# APRSTracker_GPS.net
KiCad netlist of a schematic drawn in EAGLE
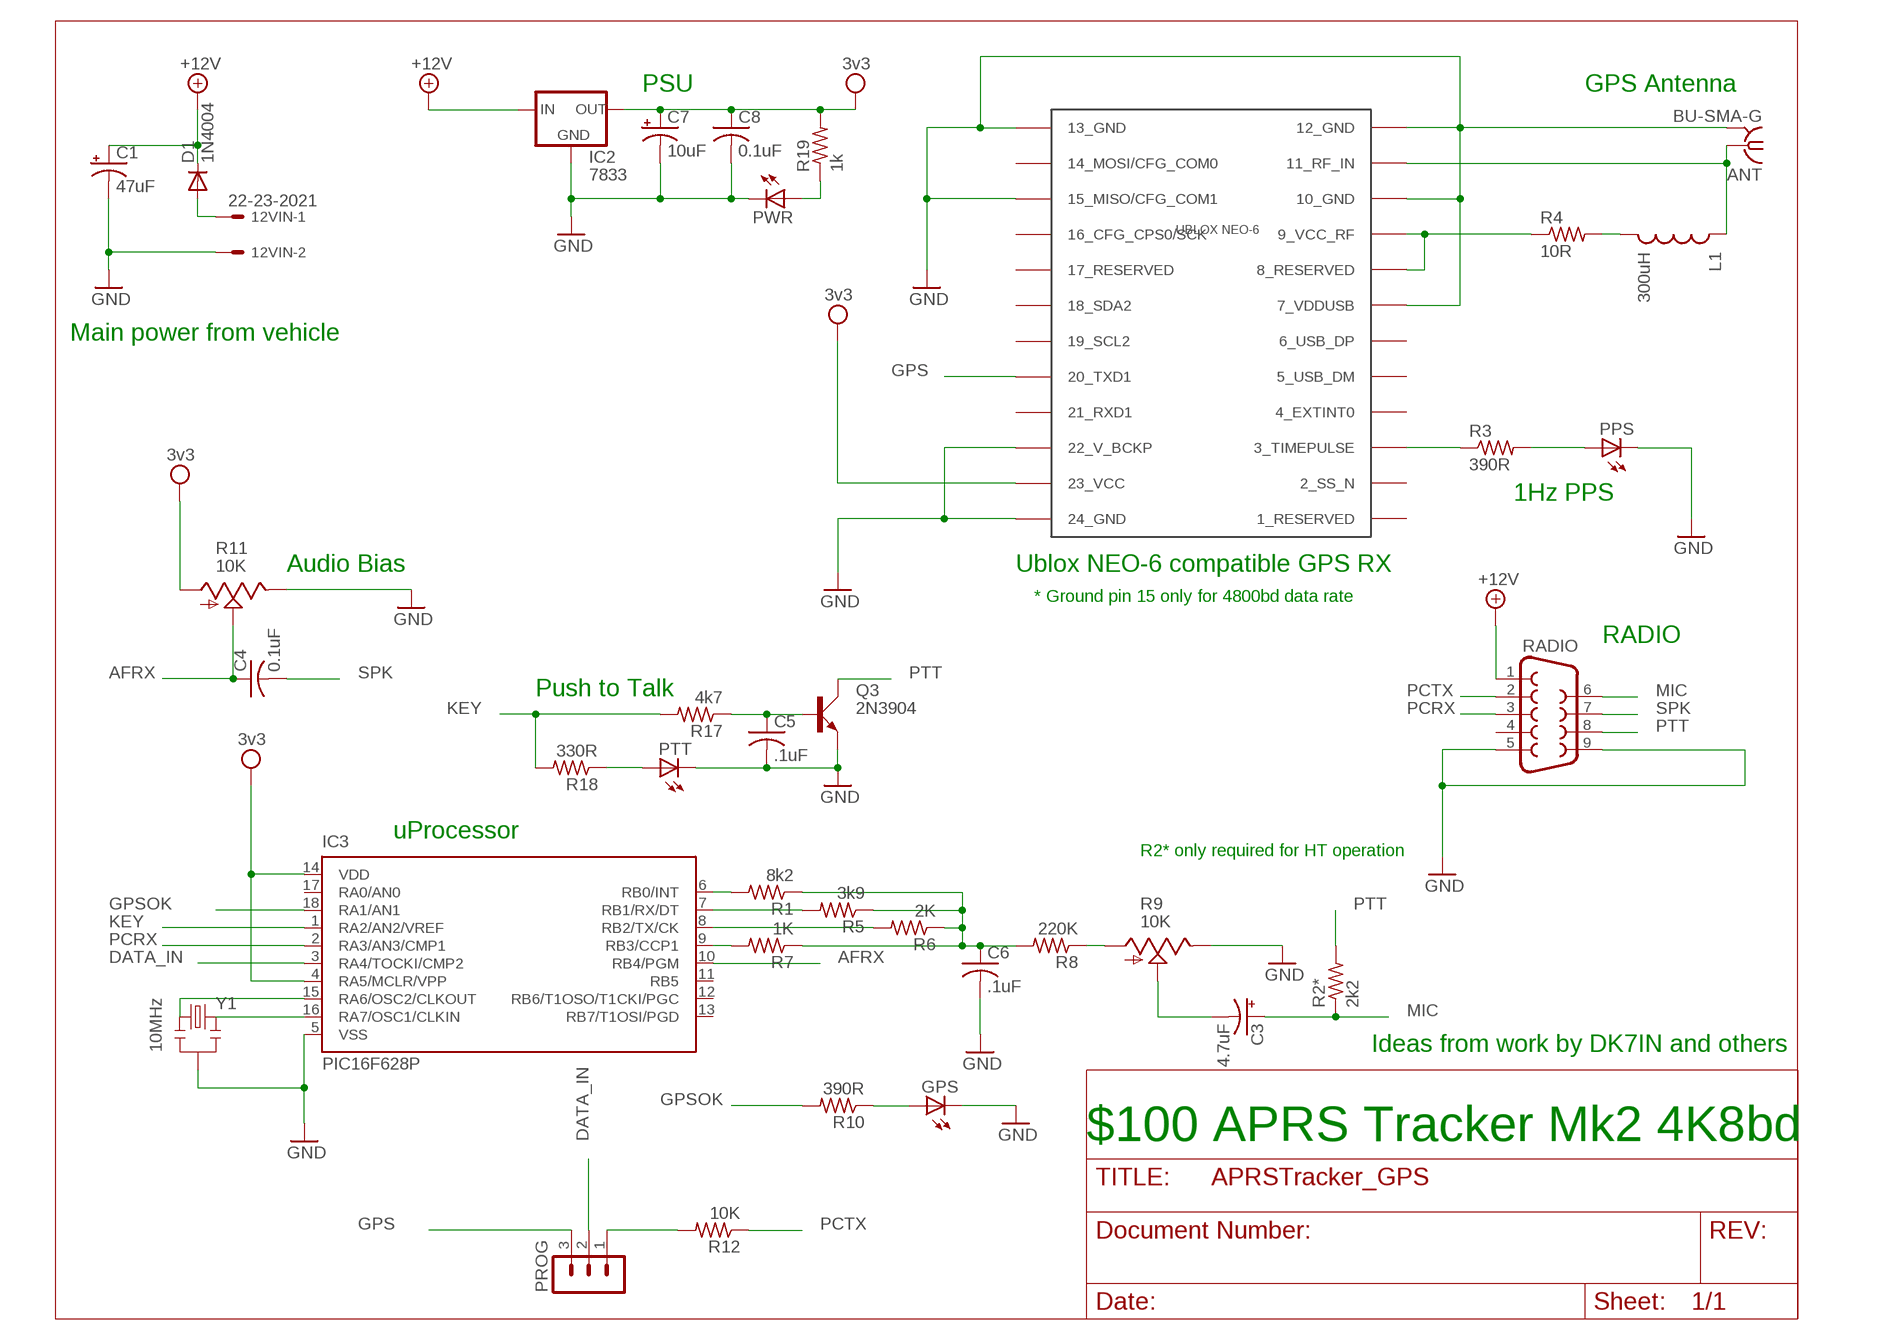
[diagram p0: schematic, sheet 1]

(export (version "E")
  (design (tool "Eeschema 10.0.6"))
  (components
    (comp (ref "12VIN")
      (value "22-23-2021")
      (footprint "eagle-import:22-23-2021")
      (fields (field (name "MF") "MOLEX"))
      (libsource (lib "eagle-import") (part "22-23-2021"))
    )
    (comp (ref "ANT")
      (value "BU-SMA-G")
      (footprint "eagle-import:BU-SMA-G")
      (libsource (lib "eagle-import") (part "BU-SMA-G"))
    )
    (comp (ref "C1")
      (value "47uF")
      (footprint "eagle-import:CPOL-RADIAL-10UF-25V")
      (libsource (lib "eagle-import") (part "CAP_POLPTH2"))
    )
    (comp (ref "C3")
      (value "4.7uF")
      (footprint "eagle-import:CPOL-RADIAL-10UF-25V")
      (libsource (lib "eagle-import") (part "CAP_POLPTH2"))
    )
    (comp (ref "C4")
      (value "0.1uF")
      (footprint "eagle-import:C025-025X050")
      (libsource (lib "eagle-import") (part "C-US025-025X050"))
    )
    (comp (ref "C5")
      (value ".1uF")
      (footprint "eagle-import:C025-025X050")
      (libsource (lib "eagle-import") (part "C-US025-025X050"))
    )
    (comp (ref "C6")
      (value ".1uF")
      (footprint "eagle-import:C025-025X050")
      (libsource (lib "eagle-import") (part "C-US025-025X050"))
    )
    (comp (ref "C7")
      (value "10uF")
      (footprint "eagle-import:CPOL-RADIAL-10UF-25V")
      (libsource (lib "eagle-import") (part "CAP_POLPTH2"))
    )
    (comp (ref "C8")
      (value "0.1uF")
      (footprint "eagle-import:C025-025X050")
      (libsource (lib "eagle-import") (part "C-US025-025X050"))
    )
    (comp (ref "D1")
      (value "1N4004")
      (footprint "eagle-import:DO41-10")
      (libsource (lib "eagle-import") (part "1N4004"))
    )
    (comp (ref "GPS")
      (value "LED3MM")
      (footprint "eagle-import:LED3MM")
      (libsource (lib "eagle-import") (part "LED3MM"))
    )
    (comp (ref "IC2")
      (value "7833")
      (footprint "eagle-import:TO-220-ALT")
      (libsource (lib "eagle-import") (part "V_REG_78XX-TO-220"))
    )
    (comp (ref "IC3")
      (value "PIC16F628P")
      (footprint "eagle-import:DIL18")
      (libsource (lib "eagle-import") (part "PIC16F62P8"))
    )
    (comp (ref "L1")
      (value "300uH")
      (footprint "eagle-import:0805")
      (libsource (lib "eagle-import") (part "INDUCTOR0805"))
    )
    (comp (ref "PPS")
      (value "LED1206")
      (footprint "eagle-import:LED-1206")
      (libsource (lib "eagle-import") (part "LED1206"))
    )
    (comp (ref "PROG")
      (value "MA03-1")
      (footprint "eagle-import:MA03-1")
      (libsource (lib "eagle-import") (part "MA03-1"))
    )
    (comp (ref "PTT")
      (value "LED3MM")
      (footprint "eagle-import:LED3MM")
      (libsource (lib "eagle-import") (part "LED3MM"))
    )
    (comp (ref "PWR")
      (value "LED3MM")
      (footprint "eagle-import:LED3MM")
      (libsource (lib "eagle-import") (part "LED3MM"))
    )
    (comp (ref "Q3")
      (value "2N3904")
      (footprint "eagle-import:TO92D")
      (libsource (lib "eagle-import") (part "2N3904"))
    )
    (comp (ref "R1")
      (value "8k2")
      (footprint "eagle-import:0207_2V")
      (libsource (lib "eagle-import") (part "R-US_0207/2V"))
    )
    (comp (ref "R2*")
      (value "2k2")
      (footprint "eagle-import:0207_2V")
      (libsource (lib "eagle-import") (part "R-US_0207/2V"))
    )
    (comp (ref "R3")
      (value "390R")
      (footprint "eagle-import:M0805")
      (libsource (lib "eagle-import") (part "R-US_M0805"))
    )
    (comp (ref "R4")
      (value "10R")
      (footprint "eagle-import:M0805")
      (libsource (lib "eagle-import") (part "R-US_M0805"))
    )
    (comp (ref "R5")
      (value "3k9")
      (footprint "eagle-import:0207_2V")
      (libsource (lib "eagle-import") (part "R-US_0207/2V"))
    )
    (comp (ref "R6")
      (value "2K")
      (footprint "eagle-import:0207_2V")
      (libsource (lib "eagle-import") (part "R-US_0207/2V"))
    )
    (comp (ref "R7")
      (value "1K")
      (footprint "eagle-import:0207_2V")
      (libsource (lib "eagle-import") (part "R-US_0207/2V"))
    )
    (comp (ref "R8")
      (value "220K")
      (footprint "eagle-import:0207_2V")
      (libsource (lib "eagle-import") (part "R-US_0207/2V"))
    )
    (comp (ref "R9")
      (value "10K")
      (footprint "eagle-import:CA6V")
      (libsource (lib "eagle-import") (part "TRIM_US-CA6V"))
    )
    (comp (ref "R10")
      (value "390R")
      (footprint "eagle-import:0207_2V")
      (libsource (lib "eagle-import") (part "R-US_0207/2V"))
    )
    (comp (ref "R11")
      (value "10K")
      (footprint "eagle-import:CA6V")
      (libsource (lib "eagle-import") (part "TRIM_US-CA6V"))
    )
    (comp (ref "R12")
      (value "10K")
      (footprint "eagle-import:0207_2V")
      (libsource (lib "eagle-import") (part "R-US_0207/2V"))
    )
    (comp (ref "R17")
      (value "4k7")
      (footprint "eagle-import:0207_2V")
      (libsource (lib "eagle-import") (part "R-US_0207/2V"))
    )
    (comp (ref "R18")
      (value "330R")
      (footprint "eagle-import:0207_2V")
      (libsource (lib "eagle-import") (part "R-US_0207/2V"))
    )
    (comp (ref "R19")
      (value "1k")
      (footprint "eagle-import:0207_2V")
      (libsource (lib "eagle-import") (part "R-US_0207/2V"))
    )
    (comp (ref "RADIO")
      (value "F09HP")
      (footprint "eagle-import:F09HP")
      (libsource (lib "eagle-import") (part "F09HP"))
    )
    (comp (ref "U$1")
      (value "UBLOX_NEO-6")
      (footprint "eagle-import:UBLOX_NEO-6P")
      (libsource (lib "eagle-import") (part "UBLOX_NEO-6"))
    )
    (comp (ref "Y1")
      (value "10MHz")
      (footprint "eagle-import:RESONATOR-PTH")
      (libsource (lib "eagle-import") (part "RESONATORPTH"))
    )
  )
  (nets
    (net (code "1") (name "+12V") (class "Default")
      (node (ref "C1") (pin "1") (pinfunction "+_1") (pintype "passive"))
      (node (ref "D1") (pin "C") (pinfunction "C_C") (pintype "passive"))
      (node (ref "IC2") (pin "IN") (pinfunction "IN_IN") (pintype "input"))
      (node (ref "RADIO") (pin "1") (pinfunction "1_1") (pintype "passive"))
    )
    (net (code "2") (name "/AFRX") (class "Default")
      (node (ref "C4") (pin "1") (pinfunction "1_1") (pintype "passive"))
      (node (ref "IC3") (pin "10") (pinfunction "RB4/PGM_10") (pintype "bidirectional"))
      (node (ref "R11") (pin "S") (pinfunction "S_S") (pintype "passive"))
    )
    (net (code "3") (name "/DATA_IN") (class "Default")
      (node (ref "IC3") (pin "3") (pinfunction "RA4/TOCKI/CMP2_3") (pintype "bidirectional"))
      (node (ref "PROG") (pin "2") (pinfunction "2_2") (pintype "passive"))
    )
    (net (code "4") (name "/GPS") (class "Default")
      (node (ref "PROG") (pin "3") (pinfunction "3_3") (pintype "passive"))
      (node (ref "U$1") (pin "20_TXD1") (pinfunction "20_TXD1_20_TXD1") (pintype "bidirectional"))
    )
    (net (code "5") (name "/GPSOK") (class "Default")
      (node (ref "IC3") (pin "18") (pinfunction "RA1/AN1_18") (pintype "bidirectional"))
      (node (ref "R10") (pin "2") (pinfunction "2_2") (pintype "passive"))
    )
    (net (code "6") (name "/KEY") (class "Default")
      (node (ref "IC3") (pin "1") (pinfunction "RA2/AN2/VREF_1") (pintype "bidirectional"))
      (node (ref "R17") (pin "2") (pinfunction "2_2") (pintype "passive"))
      (node (ref "R18") (pin "2") (pinfunction "2_2") (pintype "passive"))
    )
    (net (code "7") (name "/MIC") (class "Default")
      (node (ref "C3") (pin "1") (pinfunction "+_1") (pintype "passive"))
      (node (ref "R2*") (pin "1") (pinfunction "1_1") (pintype "passive"))
      (node (ref "RADIO") (pin "6") (pinfunction "6_6") (pintype "passive"))
    )
    (net (code "8") (name "/PCRX") (class "Default")
      (node (ref "IC3") (pin "2") (pinfunction "RA3/AN3/CMP1_2") (pintype "bidirectional"))
      (node (ref "RADIO") (pin "3") (pinfunction "3_3") (pintype "passive"))
    )
    (net (code "9") (name "/PCTX") (class "Default")
      (node (ref "R12") (pin "1") (pinfunction "1_1") (pintype "passive"))
      (node (ref "RADIO") (pin "2") (pinfunction "2_2") (pintype "passive"))
    )
    (net (code "10") (name "/PTT") (class "Default")
      (node (ref "Q3") (pin "C") (pinfunction "C_C") (pintype "passive"))
      (node (ref "R2*") (pin "2") (pinfunction "2_2") (pintype "passive"))
      (node (ref "RADIO") (pin "8") (pinfunction "8_8") (pintype "passive"))
    )
    (net (code "11") (name "/SPK") (class "Default")
      (node (ref "C4") (pin "2") (pinfunction "2_2") (pintype "passive"))
      (node (ref "RADIO") (pin "7") (pinfunction "7_7") (pintype "passive"))
    )
    (net (code "12") (name "3v3") (class "Default")
      (node (ref "C7") (pin "1") (pinfunction "+_1") (pintype "passive"))
      (node (ref "C8") (pin "1") (pinfunction "1_1") (pintype "passive"))
      (node (ref "IC2") (pin "OUT") (pinfunction "OUT_OUT") (pintype "output"))
      (node (ref "IC3") (pin "14") (pinfunction "VDD_14") (pintype "power_in"))
      (node (ref "IC3") (pin "4") (pinfunction "RA5/MCLR/VPP_4") (pintype "bidirectional"))
      (node (ref "R11") (pin "A") (pinfunction "A_A") (pintype "passive"))
      (node (ref "R19") (pin "2") (pinfunction "2_2") (pintype "passive"))
      (node (ref "U$1") (pin "23_VCC") (pinfunction "23_VCC_23_VCC") (pintype "bidirectional"))
    )
    (net (code "13") (name "GND") (class "Default")
      (node (ref "12VIN") (pin "2") (pinfunction "S_2") (pintype "passive"))
      (node (ref "ANT") (pin "2") (pinfunction "GND_2") (pintype "power_in"))
      (node (ref "C1") (pin "2") (pinfunction "-_2") (pintype "passive"))
      (node (ref "C5") (pin "2") (pinfunction "2_2") (pintype "passive"))
      (node (ref "C6") (pin "2") (pinfunction "2_2") (pintype "passive"))
      (node (ref "C7") (pin "2") (pinfunction "-_2") (pintype "passive"))
      (node (ref "C8") (pin "2") (pinfunction "2_2") (pintype "passive"))
      (node (ref "GPS") (pin "K") (pinfunction "C_K") (pintype "passive"))
      (node (ref "IC2") (pin "GND") (pinfunction "GND_GND") (pintype "input"))
      (node (ref "IC3") (pin "5") (pinfunction "VSS_5") (pintype "power_in"))
      (node (ref "PPS") (pin "C") (pinfunction "C_C") (pintype "passive"))
      (node (ref "PTT") (pin "K") (pinfunction "C_K") (pintype "passive"))
      (node (ref "PWR") (pin "K") (pinfunction "C_K") (pintype "passive"))
      (node (ref "Q3") (pin "E") (pinfunction "E_E") (pintype "passive"))
      (node (ref "R11") (pin "E") (pinfunction "E_E") (pintype "passive"))
      (node (ref "R9") (pin "E") (pinfunction "E_E") (pintype "passive"))
      (node (ref "RADIO") (pin "5") (pinfunction "5_5") (pintype "passive"))
      (node (ref "RADIO") (pin "9") (pinfunction "9_9") (pintype "passive"))
      (node (ref "U$1") (pin "10_GND") (pinfunction "10_GND_10_GND") (pintype "bidirectional"))
      (node (ref "U$1") (pin "12_GND") (pinfunction "12_GND_12_GND") (pintype "bidirectional"))
      (node (ref "U$1") (pin "13_GND") (pinfunction "13_GND_13_GND") (pintype "bidirectional"))
      (node (ref "U$1") (pin "15_MISO/CFG_COM1") (pinfunction "15_MISO/CFG_COM1_15_MISO/CFG_COM1") (pintype "bidirectional"))
      (node (ref "U$1") (pin "22_V_BCKP") (pinfunction "22_V_BCKP_22_V_BCKP") (pintype "bidirectional"))
      (node (ref "U$1") (pin "24_GND") (pinfunction "24_GND_24_GND") (pintype "bidirectional"))
      (node (ref "U$1") (pin "7_VDDUSB") (pinfunction "7_VDDUSB_7_VDDUSB") (pintype "bidirectional"))
      (node (ref "Y1") (pin "2") (pinfunction "2_2") (pintype "passive"))
    )
    (net (code "14") (name "Net-(12VINA-S)") (class "Default")
      (node (ref "12VIN") (pin "1") (pinfunction "S_1") (pintype "passive"))
      (node (ref "D1") (pin "A") (pinfunction "A_A") (pintype "passive"))
    )
    (net (code "15") (name "Net-(ANT-Pad1)") (class "Default")
      (node (ref "ANT") (pin "1") (pinfunction "1_1") (pintype "passive"))
      (node (ref "L1") (pin "1") (pinfunction "1_1") (pintype "passive"))
      (node (ref "U$1") (pin "11_RF_IN") (pinfunction "11_RF_IN_11_RF_IN") (pintype "bidirectional"))
    )
    (net (code "16") (name "Net-(C3--)") (class "Default")
      (node (ref "C3") (pin "2") (pinfunction "-_2") (pintype "passive"))
      (node (ref "R9") (pin "S") (pinfunction "S_S") (pintype "passive"))
    )
    (net (code "17") (name "Net-(C5-Pad1)") (class "Default")
      (node (ref "C5") (pin "1") (pinfunction "1_1") (pintype "passive"))
      (node (ref "Q3") (pin "B") (pinfunction "B_B") (pintype "passive"))
      (node (ref "R17") (pin "1") (pinfunction "1_1") (pintype "passive"))
    )
    (net (code "18") (name "Net-(C6-Pad1)") (class "Default")
      (node (ref "C6") (pin "1") (pinfunction "1_1") (pintype "passive"))
      (node (ref "R1") (pin "1") (pinfunction "1_1") (pintype "passive"))
      (node (ref "R5") (pin "1") (pinfunction "1_1") (pintype "passive"))
      (node (ref "R6") (pin "1") (pinfunction "1_1") (pintype "passive"))
      (node (ref "R7") (pin "1") (pinfunction "1_1") (pintype "passive"))
      (node (ref "R8") (pin "2") (pinfunction "2_2") (pintype "passive"))
    )
    (net (code "19") (name "Net-(GPS-PadA)") (class "Default")
      (node (ref "GPS") (pin "A") (pinfunction "A_A") (pintype "passive"))
      (node (ref "R10") (pin "1") (pinfunction "1_1") (pintype "passive"))
    )
    (net (code "20") (name "Net-(IC3-RA6{slash}OSC2{slash}CLKOUT)") (class "Default")
      (node (ref "IC3") (pin "15") (pinfunction "RA6/OSC2/CLKOUT_15") (pintype "bidirectional"))
      (node (ref "Y1") (pin "1") (pinfunction "1_1") (pintype "passive"))
    )
    (net (code "21") (name "Net-(IC3-RA7{slash}OSC1{slash}CLKIN)") (class "Default")
      (node (ref "IC3") (pin "16") (pinfunction "RA7/OSC1/CLKIN_16") (pintype "bidirectional"))
      (node (ref "Y1") (pin "3") (pinfunction "3_3") (pintype "passive"))
    )
    (net (code "22") (name "Net-(IC3-RB0{slash}INT)") (class "Default")
      (node (ref "IC3") (pin "6") (pinfunction "RB0/INT_6") (pintype "bidirectional"))
      (node (ref "R1") (pin "2") (pinfunction "2_2") (pintype "passive"))
    )
    (net (code "23") (name "Net-(IC3-RB1{slash}RX{slash}DT)") (class "Default")
      (node (ref "IC3") (pin "7") (pinfunction "RB1/RX/DT_7") (pintype "bidirectional"))
      (node (ref "R5") (pin "2") (pinfunction "2_2") (pintype "passive"))
    )
    (net (code "24") (name "Net-(IC3-RB2{slash}TX{slash}CK)") (class "Default")
      (node (ref "IC3") (pin "8") (pinfunction "RB2/TX/CK_8") (pintype "bidirectional"))
      (node (ref "R6") (pin "2") (pinfunction "2_2") (pintype "passive"))
    )
    (net (code "25") (name "Net-(IC3-RB3{slash}CCP1)") (class "Default")
      (node (ref "IC3") (pin "9") (pinfunction "RB3/CCP1_9") (pintype "bidirectional"))
      (node (ref "R7") (pin "2") (pinfunction "2_2") (pintype "passive"))
    )
    (net (code "26") (name "Net-(L1-Pad2)") (class "Default")
      (node (ref "L1") (pin "2") (pinfunction "2_2") (pintype "passive"))
      (node (ref "R4") (pin "2") (pinfunction "2_2") (pintype "passive"))
    )
    (net (code "27") (name "Net-(PPS-PadA)") (class "Default")
      (node (ref "PPS") (pin "A") (pinfunction "A_A") (pintype "passive"))
      (node (ref "R3") (pin "2") (pinfunction "2_2") (pintype "passive"))
    )
    (net (code "28") (name "Net-(PROG-Pad1)") (class "Default")
      (node (ref "PROG") (pin "1") (pinfunction "1_1") (pintype "passive"))
      (node (ref "R12") (pin "2") (pinfunction "2_2") (pintype "passive"))
    )
    (net (code "29") (name "Net-(PTT-PadA)") (class "Default")
      (node (ref "PTT") (pin "A") (pinfunction "A_A") (pintype "passive"))
      (node (ref "R18") (pin "1") (pinfunction "1_1") (pintype "passive"))
    )
    (net (code "30") (name "Net-(PWR-PadA)") (class "Default")
      (node (ref "PWR") (pin "A") (pinfunction "A_A") (pintype "passive"))
      (node (ref "R19") (pin "1") (pinfunction "1_1") (pintype "passive"))
    )
    (net (code "31") (name "Net-(R3-Pad1)") (class "Default")
      (node (ref "R3") (pin "1") (pinfunction "1_1") (pintype "passive"))
      (node (ref "U$1") (pin "3_TIMEPULSE") (pinfunction "3_TIMEPULSE_3_TIMEPULSE") (pintype "bidirectional"))
    )
    (net (code "32") (name "Net-(R4-Pad1)") (class "Default")
      (node (ref "R4") (pin "1") (pinfunction "1_1") (pintype "passive"))
      (node (ref "U$1") (pin "8_RESERVED") (pinfunction "8_RESERVED_8_RESERVED") (pintype "bidirectional"))
      (node (ref "U$1") (pin "9_VCC_RF") (pinfunction "9_VCC_RF_9_VCC_RF") (pintype "bidirectional"))
    )
    (net (code "33") (name "Net-(R8-Pad1)") (class "Default")
      (node (ref "R8") (pin "1") (pinfunction "1_1") (pintype "passive"))
      (node (ref "R9") (pin "A") (pinfunction "A_A") (pintype "passive"))
    )
    (net (code "34") (name "unconnected-(IC3-RA0{slash}AN0-Pad17)") (class "Default")
      (node (ref "IC3") (pin "17") (pinfunction "RA0/AN0_17") (pintype "bidirectional"))
    )
    (net (code "35") (name "unconnected-(IC3-RB5-Pad11)") (class "Default")
      (node (ref "IC3") (pin "11") (pinfunction "RB5_11") (pintype "bidirectional"))
    )
    (net (code "36") (name "unconnected-(IC3-RB6{slash}T1OSO{slash}T1CKI{slash}PGC-Pad12)") (class "Default")
      (node (ref "IC3") (pin "12") (pinfunction "RB6/T1OSO/T1CKI/PGC_12") (pintype "bidirectional"))
    )
    (net (code "37") (name "unconnected-(IC3-RB7{slash}T1OSI{slash}PGD-Pad13)") (class "Default")
      (node (ref "IC3") (pin "13") (pinfunction "RB7/T1OSI/PGD_13") (pintype "bidirectional"))
    )
    (net (code "38") (name "unconnected-(RADIO-Pad4)") (class "Default")
      (node (ref "RADIO") (pin "4") (pinfunction "4_4") (pintype "passive"))
    )
    (net (code "39") (name "unconnected-(U$1-Pad1_RESERVED)") (class "Default")
      (node (ref "U$1") (pin "1_RESERVED") (pinfunction "1_RESERVED_1_RESERVED") (pintype "bidirectional"))
    )
    (net (code "40") (name "unconnected-(U$1-Pad2_SS_N)") (class "Default")
      (node (ref "U$1") (pin "2_SS_N") (pinfunction "2_SS_N_2_SS_N") (pintype "bidirectional"))
    )
    (net (code "41") (name "unconnected-(U$1-Pad4_EXTINT0)") (class "Default")
      (node (ref "U$1") (pin "4_EXTINT0") (pinfunction "4_EXTINT0_4_EXTINT0") (pintype "bidirectional"))
    )
    (net (code "42") (name "unconnected-(U$1-Pad5_USB_DM)") (class "Default")
      (node (ref "U$1") (pin "5_USB_DM") (pinfunction "5_USB_DM_5_USB_DM") (pintype "bidirectional"))
    )
    (net (code "43") (name "unconnected-(U$1-Pad6_USB_DP)") (class "Default")
      (node (ref "U$1") (pin "6_USB_DP") (pinfunction "6_USB_DP_6_USB_DP") (pintype "bidirectional"))
    )
    (net (code "44") (name "unconnected-(U$1-Pad14_MOSI{slash}CFG_COM0)") (class "Default")
      (node (ref "U$1") (pin "14_MOSI/CFG_COM0") (pinfunction "14_MOSI/CFG_COM0_14_MOSI/CFG_COM0") (pintype "bidirectional"))
    )
    (net (code "45") (name "unconnected-(U$1-Pad16_CFG_CPS0{slash}SCK)") (class "Default")
      (node (ref "U$1") (pin "16_CFG_CPS0/SCK") (pinfunction "16_CFG_CPS0/SCK_16_CFG_CPS0/SCK") (pintype "bidirectional"))
    )
    (net (code "46") (name "unconnected-(U$1-Pad17_RESERVED)") (class "Default")
      (node (ref "U$1") (pin "17_RESERVED") (pinfunction "17_RESERVED_17_RESERVED") (pintype "bidirectional"))
    )
    (net (code "47") (name "unconnected-(U$1-Pad18_SDA2)") (class "Default")
      (node (ref "U$1") (pin "18_SDA2") (pinfunction "18_SDA2_18_SDA2") (pintype "bidirectional"))
    )
    (net (code "48") (name "unconnected-(U$1-Pad19_SCL2)") (class "Default")
      (node (ref "U$1") (pin "19_SCL2") (pinfunction "19_SCL2_19_SCL2") (pintype "bidirectional"))
    )
    (net (code "49") (name "unconnected-(U$1-Pad21_RXD1)") (class "Default")
      (node (ref "U$1") (pin "21_RXD1") (pinfunction "21_RXD1_21_RXD1") (pintype "bidirectional"))
    )
  )
)
